# can-municator-board.net
KiCad netlist of a schematic drawn in EasyEDA
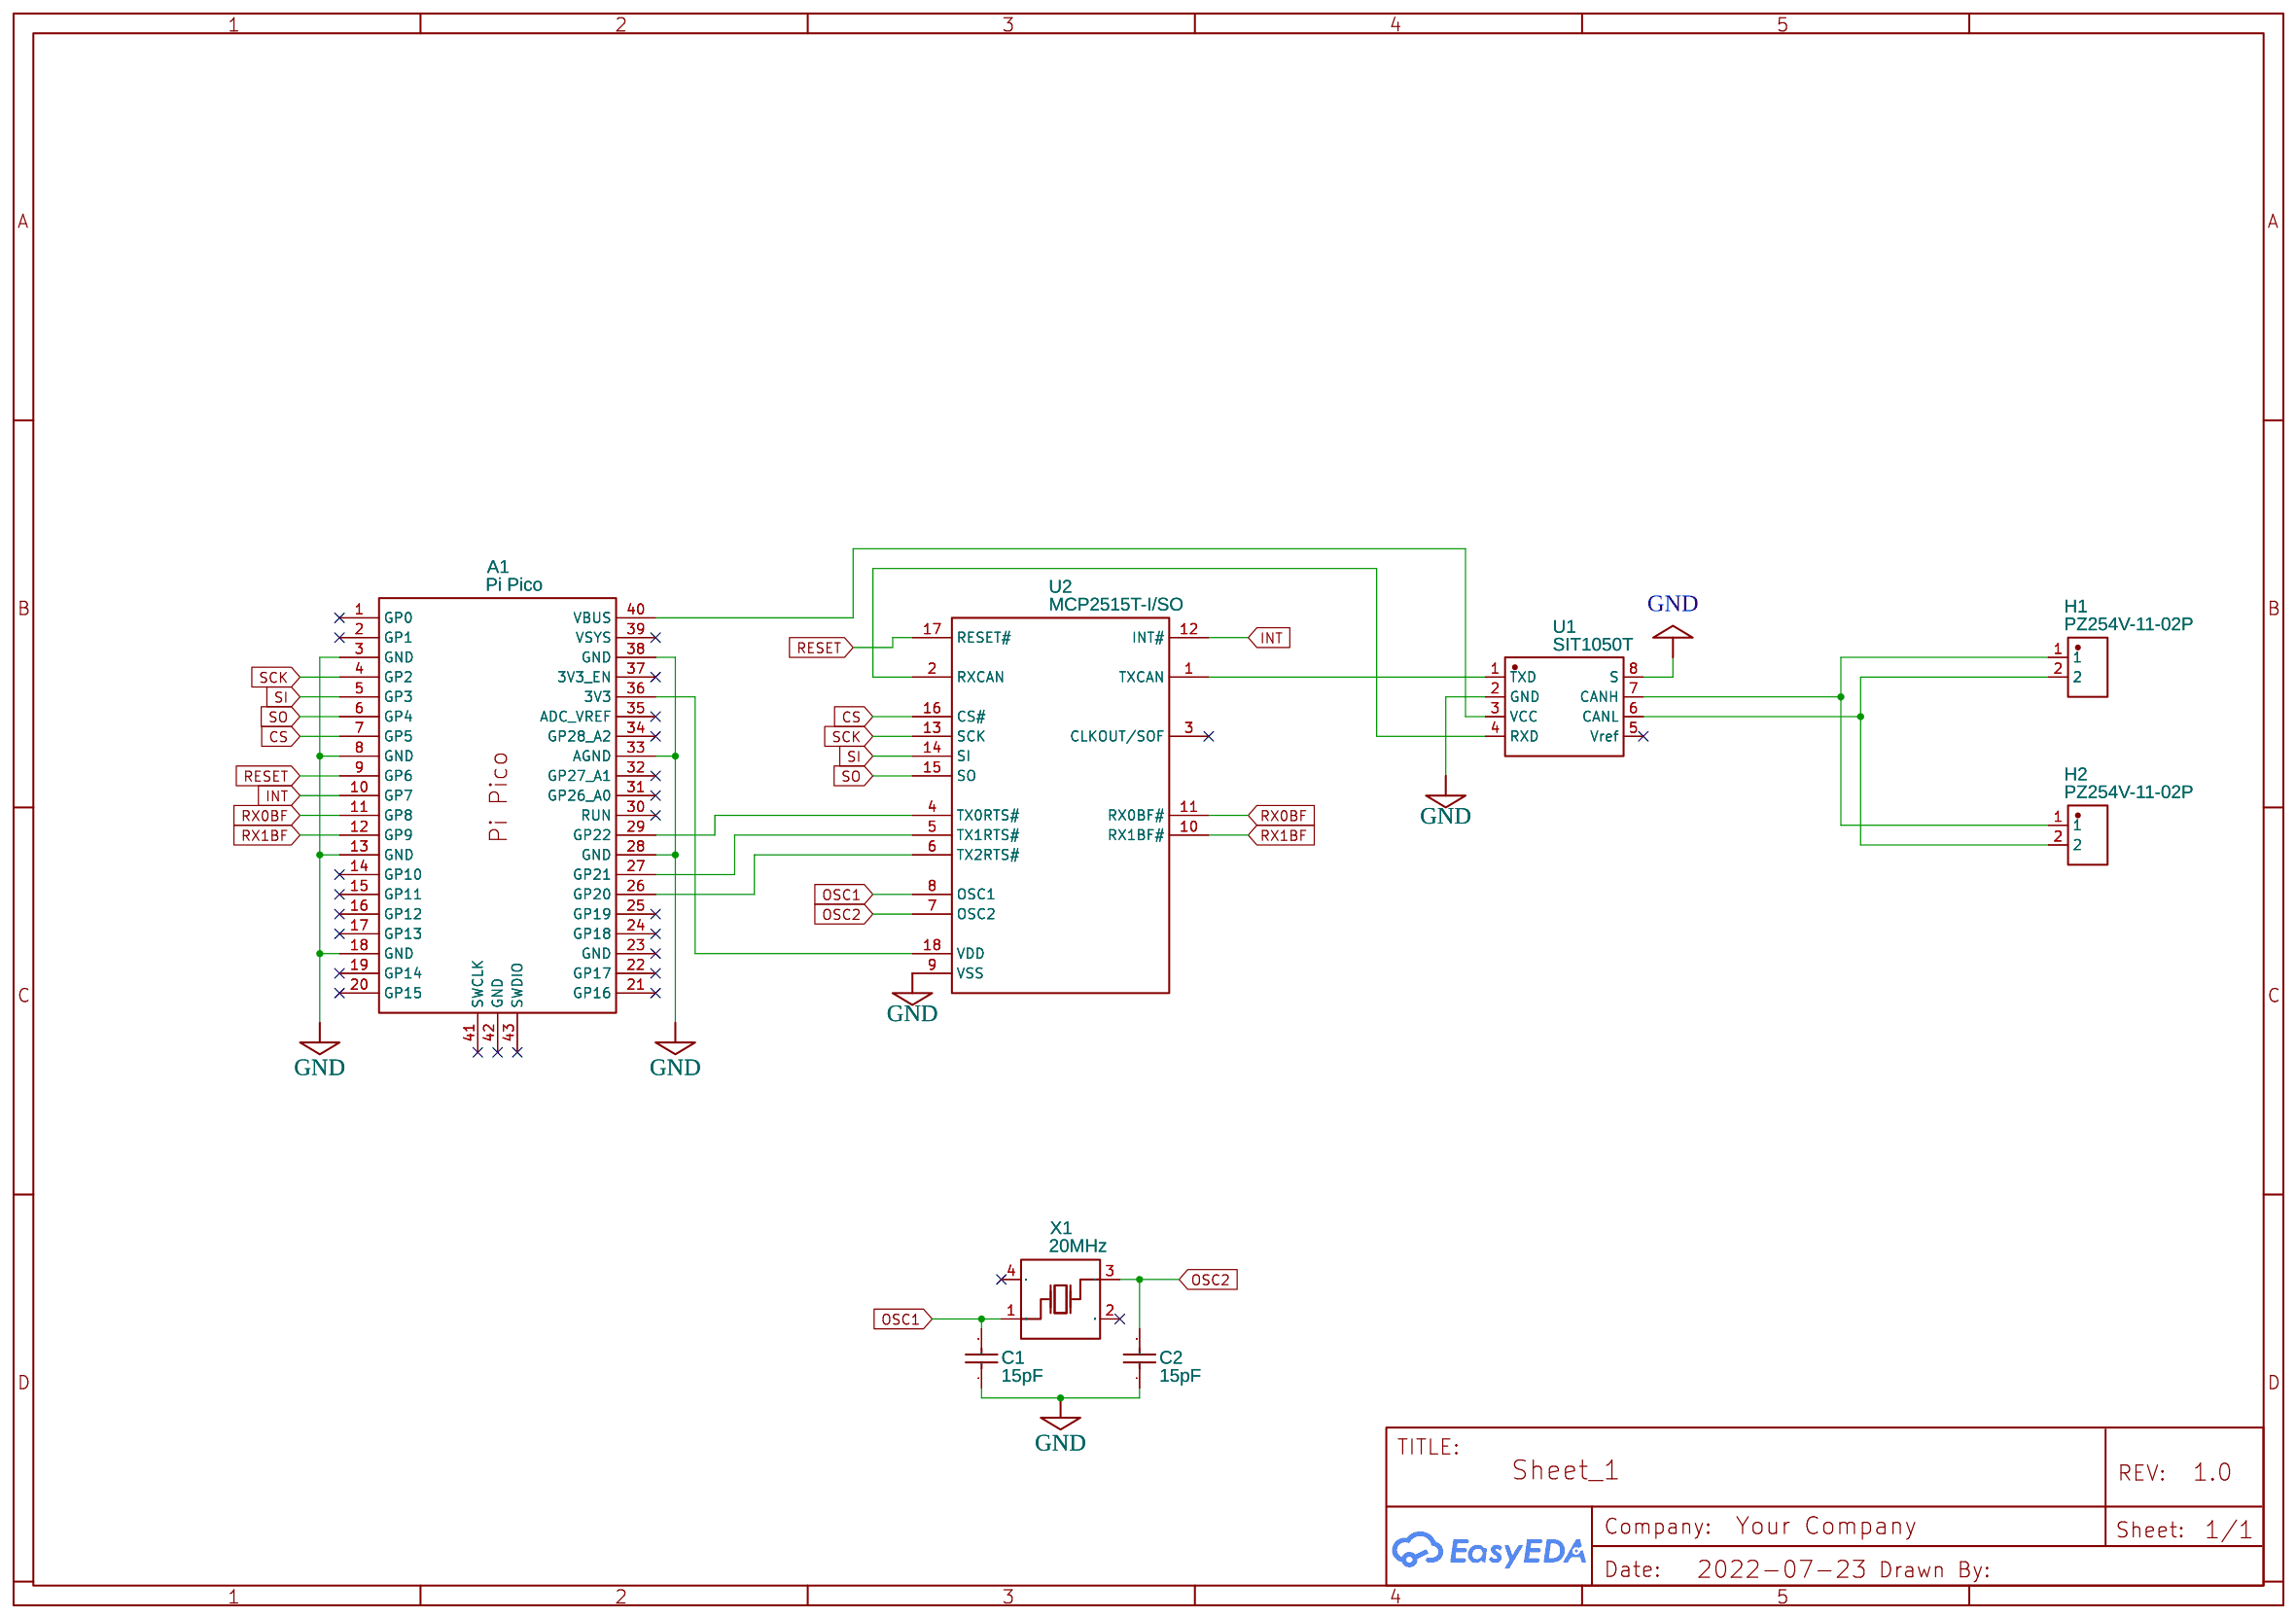
[diagram p0: schematic sheet]

(export (version "E")
  (design (tool "Eeschema 10.0.6"))
  (components
    (comp (ref "A1")
      (value "Pi Pico")
      (fields
        (field (name "BOM_Manufacturer Part") "SC0915")
        (field (name "BOM_Supplier Part") "2648-SC0915TR-ND")
      )
      (libsource (lib "") (part "Pi Pico"))
    )
    (comp (ref "C1")
      (value "15pF")
      (fields
        (field (name "BOM_Manufacturer Part") "0402CG150J500NT")
        (field (name "BOM_Supplier Part") "C1548")
      )
      (libsource (lib "") (part "0402CG150J500NT"))
    )
    (comp (ref "C2")
      (value "15pF")
      (fields
        (field (name "BOM_Manufacturer Part") "0402CG150J500NT")
        (field (name "BOM_Supplier Part") "C1548")
      )
      (libsource (lib "") (part "0402CG150J500NT"))
    )
    (comp (ref "H1")
      (value "PZ254V-11-02P")
      (fields (field (name "BOM_Supplier Part") "C492401"))
      (libsource (lib "") (part "PZ254V-11-02P"))
    )
    (comp (ref "H2")
      (value "PZ254V-11-02P")
      (fields (field (name "BOM_Supplier Part") "C492401"))
      (libsource (lib "") (part "PZ254V-11-02P"))
    )
    (comp (ref "U1")
      (value "SIT1050T")
      (fields (field (name "BOM_Supplier Part") "C313021"))
      (libsource (lib "") (part "SIT1050T"))
    )
    (comp (ref "U2")
      (value "MCP2515T-I/SO")
      (fields (field (name "BOM_Supplier Part") "C153782"))
      (libsource (lib "") (part "MCP2515T-I/SO"))
    )
    (comp (ref "X1")
      (value "20MHz")
      (fields
        (field (name "BOM_Manufacturer Part") "X322520MSB4SI")
        (field (name "BOM_Supplier Part") "C9004")
      )
      (libsource (lib "") (part "X322520MSB4SI"))
    )
  )
  (nets
    (net (code "1") (name "CS") (class "Default")
      (node (ref "A1") (pin "7") (pinfunction "GP5_7") (pintype "unspecified"))
      (node (ref "U2") (pin "16") (pinfunction "CS#_16") (pintype "unspecified"))
    )
    (net (code "2") (name "GND") (class "Default")
      (node (ref "A1") (pin "13") (pinfunction "GND_13") (pintype "unspecified"))
      (node (ref "A1") (pin "18") (pinfunction "GND_18") (pintype "unspecified"))
      (node (ref "A1") (pin "28") (pinfunction "GND_28") (pintype "unspecified"))
      (node (ref "A1") (pin "3") (pinfunction "GND_3") (pintype "unspecified"))
      (node (ref "A1") (pin "33") (pinfunction "AGND_33") (pintype "unspecified"))
      (node (ref "A1") (pin "38") (pinfunction "GND_38") (pintype "unspecified"))
      (node (ref "A1") (pin "8") (pinfunction "GND_8") (pintype "unspecified"))
      (node (ref "C1") (pin "1") (pinfunction "1_1") (pintype "input"))
      (node (ref "C2") (pin "1") (pinfunction "1_1") (pintype "input"))
      (node (ref "U1") (pin "2") (pinfunction "GND_2") (pintype "unspecified"))
      (node (ref "U1") (pin "8") (pinfunction "S_8") (pintype "unspecified"))
      (node (ref "U2") (pin "9") (pinfunction "VSS_9") (pintype "passive"))
    )
    (net (code "3") (name "INT") (class "Default")
      (node (ref "A1") (pin "10") (pinfunction "GP7_10") (pintype "unspecified"))
      (node (ref "U2") (pin "12") (pinfunction "INT#_12") (pintype "output"))
    )
    (net (code "4") (name "Net-(A1-3V3)") (class "Default")
      (node (ref "A1") (pin "36") (pinfunction "3V3_36") (pintype "unspecified"))
      (node (ref "U2") (pin "18") (pinfunction "VDD_18") (pintype "passive"))
    )
    (net (code "5") (name "Net-(A1-GP20)") (class "Default")
      (node (ref "A1") (pin "26") (pinfunction "GP20_26") (pintype "unspecified"))
      (node (ref "U2") (pin "6") (pinfunction "TX2RTS#_6") (pintype "unspecified"))
    )
    (net (code "6") (name "Net-(A1-GP21)") (class "Default")
      (node (ref "A1") (pin "27") (pinfunction "GP21_27") (pintype "unspecified"))
      (node (ref "U2") (pin "5") (pinfunction "TX1RTS#_5") (pintype "unspecified"))
    )
    (net (code "7") (name "Net-(A1-GP22)") (class "Default")
      (node (ref "A1") (pin "29") (pinfunction "GP22_29") (pintype "unspecified"))
      (node (ref "U2") (pin "4") (pinfunction "TX0RTS#_4") (pintype "unspecified"))
    )
    (net (code "8") (name "Net-(A1-VBUS)") (class "Default")
      (node (ref "A1") (pin "40") (pinfunction "VBUS_40") (pintype "unspecified"))
      (node (ref "U1") (pin "3") (pinfunction "VCC_3") (pintype "unspecified"))
    )
    (net (code "9") (name "Net-(U1-CANH)") (class "Default")
      (node (ref "H1") (pin "1") (pinfunction "1_1") (pintype "unspecified"))
      (node (ref "H2") (pin "1") (pinfunction "1_1") (pintype "unspecified"))
      (node (ref "U1") (pin "7") (pinfunction "CANH_7") (pintype "unspecified"))
    )
    (net (code "10") (name "Net-(U1-CANL)") (class "Default")
      (node (ref "H1") (pin "2") (pinfunction "2_2") (pintype "unspecified"))
      (node (ref "H2") (pin "2") (pinfunction "2_2") (pintype "unspecified"))
      (node (ref "U1") (pin "6") (pinfunction "CANL_6") (pintype "unspecified"))
    )
    (net (code "11") (name "Net-(U1-RXD)") (class "Default")
      (node (ref "U1") (pin "4") (pinfunction "RXD_4") (pintype "unspecified"))
      (node (ref "U2") (pin "2") (pinfunction "RXCAN_2") (pintype "unspecified"))
    )
    (net (code "12") (name "Net-(U1-TXD)") (class "Default")
      (node (ref "U1") (pin "1") (pinfunction "TXD_1") (pintype "unspecified"))
      (node (ref "U2") (pin "1") (pinfunction "TXCAN_1") (pintype "output"))
    )
    (net (code "13") (name "OSC1") (class "Default")
      (node (ref "C1") (pin "2") (pinfunction "2_2") (pintype "input"))
      (node (ref "U2") (pin "8") (pinfunction "OSC1_8") (pintype "unspecified"))
      (node (ref "X1") (pin "1") (pinfunction "OSC1_1") (pintype "unspecified"))
    )
    (net (code "14") (name "OSC2") (class "Default")
      (node (ref "C2") (pin "2") (pinfunction "2_2") (pintype "input"))
      (node (ref "U2") (pin "7") (pinfunction "OSC2_7") (pintype "output"))
      (node (ref "X1") (pin "3") (pinfunction "OSC2_3") (pintype "unspecified"))
    )
    (net (code "15") (name "RESET") (class "Default")
      (node (ref "A1") (pin "9") (pinfunction "GP6_9") (pintype "unspecified"))
      (node (ref "U2") (pin "17") (pinfunction "RESET#_17") (pintype "unspecified"))
    )
    (net (code "16") (name "RX0BF") (class "Default")
      (node (ref "A1") (pin "11") (pinfunction "GP8_11") (pintype "unspecified"))
      (node (ref "U2") (pin "11") (pinfunction "RX0BF#_11") (pintype "output"))
    )
    (net (code "17") (name "RX1BF") (class "Default")
      (node (ref "A1") (pin "12") (pinfunction "GP9_12") (pintype "unspecified"))
      (node (ref "U2") (pin "10") (pinfunction "RX1BF#_10") (pintype "output"))
    )
    (net (code "18") (name "SCK") (class "Default")
      (node (ref "A1") (pin "4") (pinfunction "GP2_4") (pintype "unspecified"))
      (node (ref "U2") (pin "13") (pinfunction "SCK_13") (pintype "unspecified"))
    )
    (net (code "19") (name "SI") (class "Default")
      (node (ref "A1") (pin "5") (pinfunction "GP3_5") (pintype "unspecified"))
      (node (ref "U2") (pin "14") (pinfunction "SI_14") (pintype "unspecified"))
    )
    (net (code "20") (name "SO") (class "Default")
      (node (ref "A1") (pin "6") (pinfunction "GP4_6") (pintype "unspecified"))
      (node (ref "U2") (pin "15") (pinfunction "SO_15") (pintype "output"))
    )
    (net (code "21") (name "unconnected-(A1-3V3_EN-Pad37)") (class "Default")
      (node (ref "A1") (pin "37") (pinfunction "3V3_EN_37") (pintype "unspecified+no_connect"))
    )
    (net (code "22") (name "unconnected-(A1-ADC_VREF-Pad35)") (class "Default")
      (node (ref "A1") (pin "35") (pinfunction "ADC_VREF_35") (pintype "unspecified+no_connect"))
    )
    (net (code "23") (name "unconnected-(A1-GND-Pad23)") (class "Default")
      (node (ref "A1") (pin "23") (pinfunction "GND_23") (pintype "unspecified+no_connect"))
    )
    (net (code "24") (name "unconnected-(A1-GND-Pad42)") (class "Default")
      (node (ref "A1") (pin "42") (pinfunction "GND_42") (pintype "unspecified+no_connect"))
    )
    (net (code "25") (name "unconnected-(A1-GP0-Pad1)") (class "Default")
      (node (ref "A1") (pin "1") (pinfunction "GP0_1") (pintype "unspecified+no_connect"))
    )
    (net (code "26") (name "unconnected-(A1-GP1-Pad2)") (class "Default")
      (node (ref "A1") (pin "2") (pinfunction "GP1_2") (pintype "unspecified+no_connect"))
    )
    (net (code "27") (name "unconnected-(A1-GP10-Pad14)") (class "Default")
      (node (ref "A1") (pin "14") (pinfunction "GP10_14") (pintype "unspecified+no_connect"))
    )
    (net (code "28") (name "unconnected-(A1-GP11-Pad15)") (class "Default")
      (node (ref "A1") (pin "15") (pinfunction "GP11_15") (pintype "unspecified+no_connect"))
    )
    (net (code "29") (name "unconnected-(A1-GP12-Pad16)") (class "Default")
      (node (ref "A1") (pin "16") (pinfunction "GP12_16") (pintype "unspecified+no_connect"))
    )
    (net (code "30") (name "unconnected-(A1-GP13-Pad17)") (class "Default")
      (node (ref "A1") (pin "17") (pinfunction "GP13_17") (pintype "unspecified+no_connect"))
    )
    (net (code "31") (name "unconnected-(A1-GP14-Pad19)") (class "Default")
      (node (ref "A1") (pin "19") (pinfunction "GP14_19") (pintype "unspecified+no_connect"))
    )
    (net (code "32") (name "unconnected-(A1-GP15-Pad20)") (class "Default")
      (node (ref "A1") (pin "20") (pinfunction "GP15_20") (pintype "unspecified+no_connect"))
    )
    (net (code "33") (name "unconnected-(A1-GP16-Pad21)") (class "Default")
      (node (ref "A1") (pin "21") (pinfunction "GP16_21") (pintype "unspecified+no_connect"))
    )
    (net (code "34") (name "unconnected-(A1-GP17-Pad22)") (class "Default")
      (node (ref "A1") (pin "22") (pinfunction "GP17_22") (pintype "unspecified+no_connect"))
    )
    (net (code "35") (name "unconnected-(A1-GP18-Pad24)") (class "Default")
      (node (ref "A1") (pin "24") (pinfunction "GP18_24") (pintype "unspecified+no_connect"))
    )
    (net (code "36") (name "unconnected-(A1-GP19-Pad25)") (class "Default")
      (node (ref "A1") (pin "25") (pinfunction "GP19_25") (pintype "unspecified+no_connect"))
    )
    (net (code "37") (name "unconnected-(A1-GP26_A0-Pad31)") (class "Default")
      (node (ref "A1") (pin "31") (pinfunction "GP26_A0_31") (pintype "unspecified+no_connect"))
    )
    (net (code "38") (name "unconnected-(A1-GP27_A1-Pad32)") (class "Default")
      (node (ref "A1") (pin "32") (pinfunction "GP27_A1_32") (pintype "unspecified+no_connect"))
    )
    (net (code "39") (name "unconnected-(A1-GP28_A2-Pad34)") (class "Default")
      (node (ref "A1") (pin "34") (pinfunction "GP28_A2_34") (pintype "unspecified+no_connect"))
    )
    (net (code "40") (name "unconnected-(A1-RUN-Pad30)") (class "Default")
      (node (ref "A1") (pin "30") (pinfunction "RUN_30") (pintype "unspecified+no_connect"))
    )
    (net (code "41") (name "unconnected-(A1-SWCLK-Pad41)") (class "Default")
      (node (ref "A1") (pin "41") (pinfunction "SWCLK_41") (pintype "unspecified+no_connect"))
    )
    (net (code "42") (name "unconnected-(A1-SWDIO-Pad43)") (class "Default")
      (node (ref "A1") (pin "43") (pinfunction "SWDIO_43") (pintype "unspecified+no_connect"))
    )
    (net (code "43") (name "unconnected-(A1-VSYS-Pad39)") (class "Default")
      (node (ref "A1") (pin "39") (pinfunction "VSYS_39") (pintype "unspecified+no_connect"))
    )
    (net (code "44") (name "unconnected-(U1-Vref-Pad5)") (class "Default")
      (node (ref "U1") (pin "5") (pinfunction "Vref_5") (pintype "unspecified+no_connect"))
    )
    (net (code "45") (name "unconnected-(U2-CLKOUT{slash}SOF-Pad3)") (class "Default")
      (node (ref "U2") (pin "3") (pinfunction "CLKOUT/SOF_3") (pintype "output+no_connect"))
    )
    (net (code "46") (name "unconnected-(X1-GND-Pad2)") (class "Default")
      (node (ref "X1") (pin "2") (pinfunction "GND_2") (pintype "unspecified+no_connect"))
    )
    (net (code "47") (name "unconnected-(X1-GND-Pad4)") (class "Default")
      (node (ref "X1") (pin "4") (pinfunction "GND_4") (pintype "unspecified+no_connect"))
    )
  )
)
